# BaseProximity.net
KiCad netlist of a schematic drawn in EAGLE
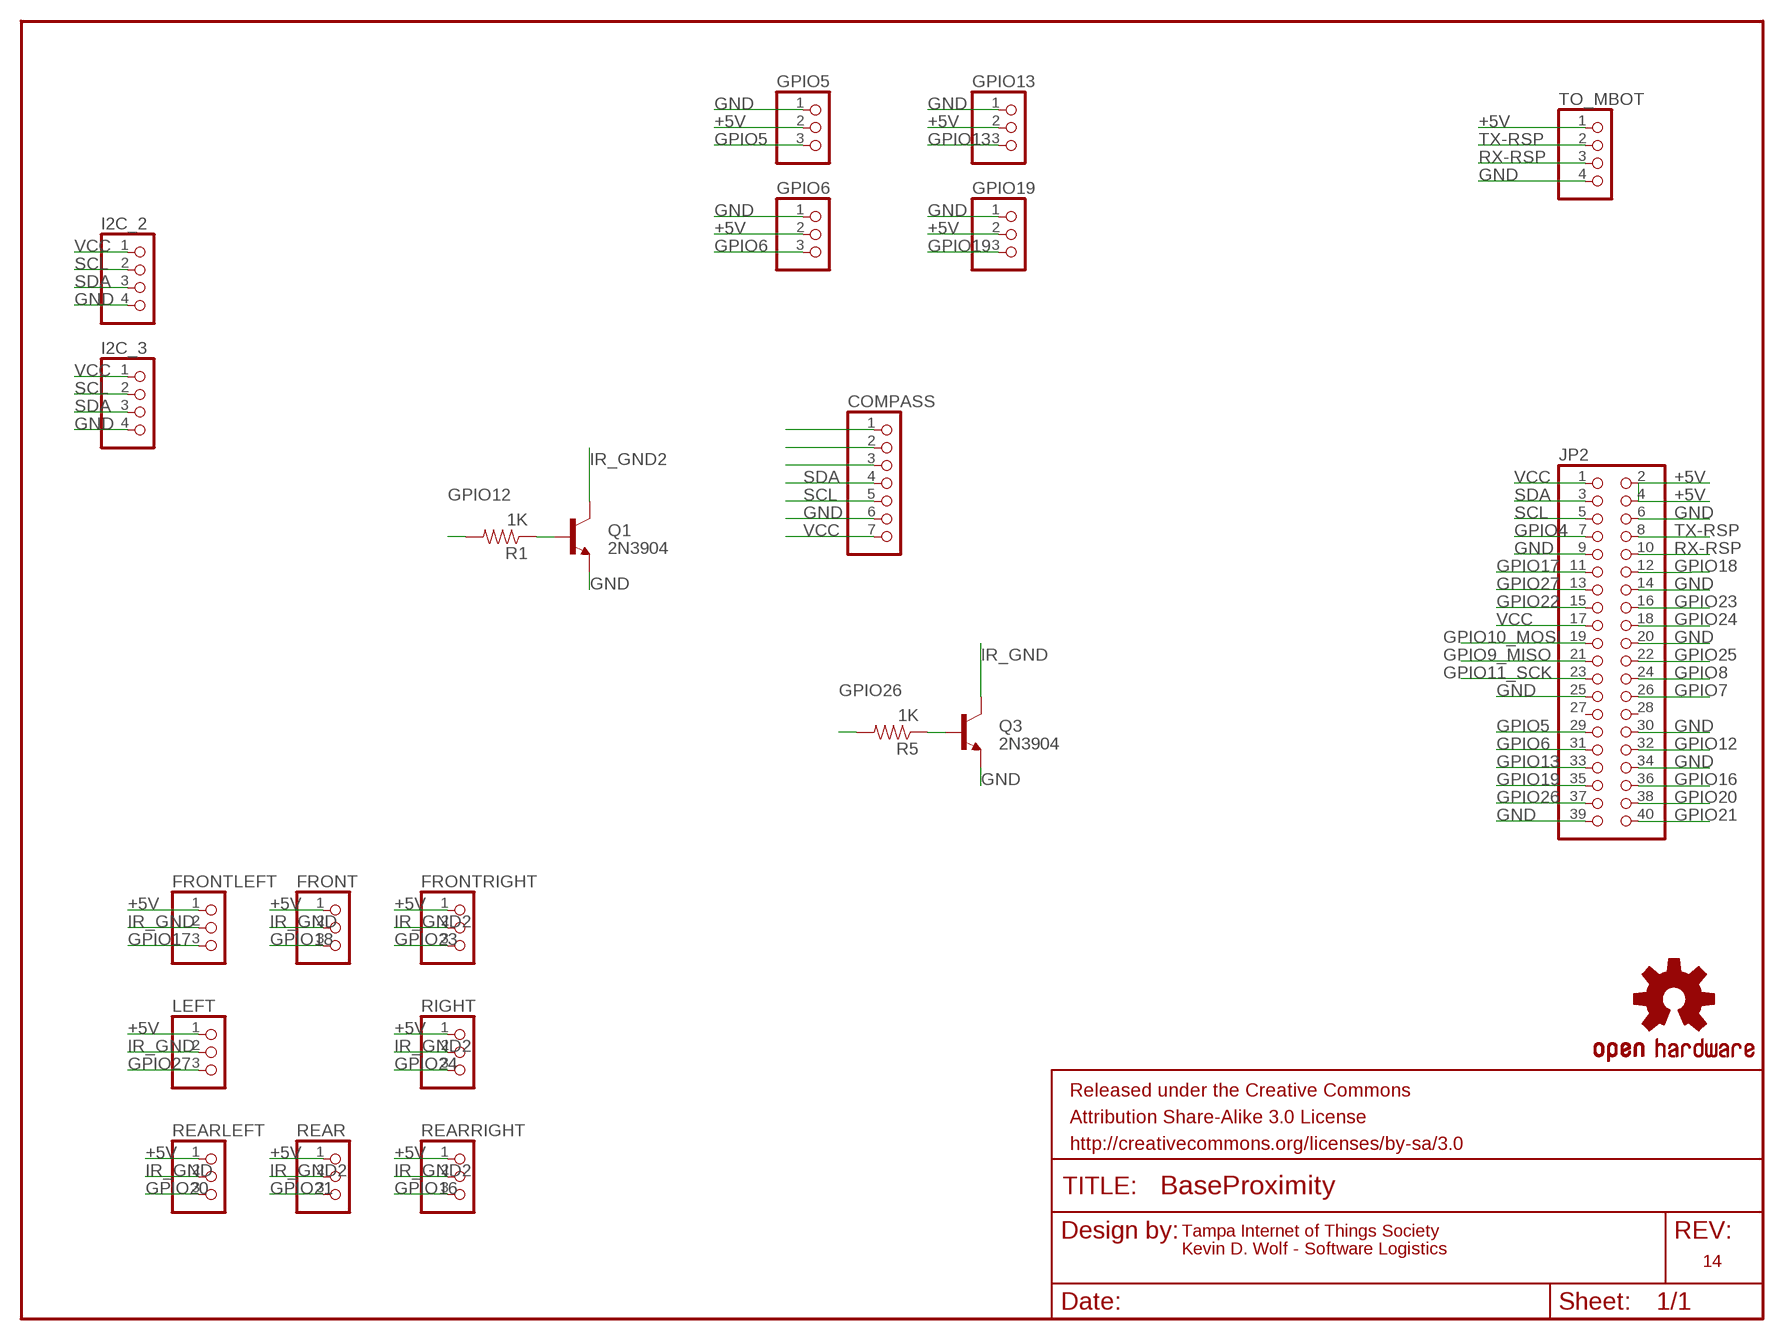
[diagram p0: schematic, sheet 1]

(export (version "E")
  (design (tool "Eeschema 10.0.6"))
  (components
    (comp (ref "COMPASS")
      (value "PINHD-1X7")
      (footprint "eagle-import:1X07")
      (libsource (lib "eagle-import") (part "PINHD-1X7"))
    )
    (comp (ref "FRAME1")
      (value "FRAME-LETTER")
      (footprint "eagle-import:CREATIVE_COMMONS")
      (libsource (lib "eagle-import") (part "FRAME-LETTER"))
    )
    (comp (ref "FRONT")
      (value "PINHD-1X3")
      (footprint "eagle-import:1X03")
      (libsource (lib "eagle-import") (part "PINHD-1X3"))
    )
    (comp (ref "FRONTLEFT")
      (value "PINHD-1X3")
      (footprint "eagle-import:1X03")
      (libsource (lib "eagle-import") (part "PINHD-1X3"))
    )
    (comp (ref "FRONTRIGHT")
      (value "PINHD-1X3")
      (footprint "eagle-import:1X03")
      (libsource (lib "eagle-import") (part "PINHD-1X3"))
    )
    (comp (ref "GPIO5")
      (value "PINHD-1X3")
      (footprint "eagle-import:1X03")
      (libsource (lib "eagle-import") (part "PINHD-1X3"))
    )
    (comp (ref "GPIO6")
      (value "PINHD-1X3")
      (footprint "eagle-import:1X03")
      (libsource (lib "eagle-import") (part "PINHD-1X3"))
    )
    (comp (ref "GPIO13")
      (value "PINHD-1X3")
      (footprint "eagle-import:1X03")
      (libsource (lib "eagle-import") (part "PINHD-1X3"))
    )
    (comp (ref "GPIO19")
      (value "PINHD-1X3")
      (footprint "eagle-import:1X03")
      (libsource (lib "eagle-import") (part "PINHD-1X3"))
    )
    (comp (ref "I2C_2")
      (value "PINHD-1X4")
      (footprint "eagle-import:1X04")
      (libsource (lib "eagle-import") (part "PINHD-1X4"))
    )
    (comp (ref "I2C_3")
      (value "PINHD-1X4")
      (footprint "eagle-import:1X04")
      (libsource (lib "eagle-import") (part "PINHD-1X4"))
    )
    (comp (ref "JP2")
      (value "PINHD-2X20")
      (footprint "eagle-import:2X20")
      (libsource (lib "eagle-import") (part "PINHD-2X20"))
    )
    (comp (ref "LEFT")
      (value "PINHD-1X3")
      (footprint "eagle-import:1X03")
      (libsource (lib "eagle-import") (part "PINHD-1X3"))
    )
    (comp (ref "Q1")
      (value "2N3904")
      (footprint "eagle-import:TO-92-EZ")
      (libsource (lib "eagle-import") (part "TRANSISTOR_NPN2N3904-EZ"))
    )
    (comp (ref "Q3")
      (value "2N3904")
      (footprint "eagle-import:TO-92-EZ")
      (libsource (lib "eagle-import") (part "TRANSISTOR_NPN2N3904-EZ"))
    )
    (comp (ref "R1")
      (value "1K")
      (footprint "eagle-import:AXIAL-0.3EZ")
      (libsource (lib "eagle-import") (part "1KOHM-1/4W-1%(PTH)HORIZ-KIT"))
    )
    (comp (ref "R5")
      (value "1K")
      (footprint "eagle-import:AXIAL-0.3EZ")
      (libsource (lib "eagle-import") (part "1KOHM-1/4W-1%(PTH)HORIZ-KIT"))
    )
    (comp (ref "REAR")
      (value "PINHD-1X3")
      (footprint "eagle-import:1X03")
      (libsource (lib "eagle-import") (part "PINHD-1X3"))
    )
    (comp (ref "REARLEFT")
      (value "PINHD-1X3")
      (footprint "eagle-import:1X03")
      (libsource (lib "eagle-import") (part "PINHD-1X3"))
    )
    (comp (ref "REARRIGHT")
      (value "PINHD-1X3")
      (footprint "eagle-import:1X03")
      (libsource (lib "eagle-import") (part "PINHD-1X3"))
    )
    (comp (ref "RIGHT")
      (value "PINHD-1X3")
      (footprint "eagle-import:1X03")
      (libsource (lib "eagle-import") (part "PINHD-1X3"))
    )
    (comp (ref "TO_MBOT")
      (value "PINHD-1X4")
      (footprint "eagle-import:1X04")
      (libsource (lib "eagle-import") (part "PINHD-1X4"))
    )
    (comp (ref "U$3")
      (value "OSHW-LOGOS")
      (footprint "eagle-import:OSHW-LOGO-S")
      (libsource (lib "eagle-import") (part "OSHW-LOGOS"))
    )
  )
  (nets
    (net (code "1") (name "/+5V") (class "Default")
      (node (ref "FRONT") (pin "1") (pinfunction "1_1") (pintype "passive"))
      (node (ref "FRONTLEFT") (pin "1") (pinfunction "1_1") (pintype "passive"))
      (node (ref "FRONTRIGHT") (pin "1") (pinfunction "1_1") (pintype "passive"))
      (node (ref "GPIO13") (pin "2") (pinfunction "2_2") (pintype "passive"))
      (node (ref "GPIO19") (pin "2") (pinfunction "2_2") (pintype "passive"))
      (node (ref "GPIO5") (pin "2") (pinfunction "2_2") (pintype "passive"))
      (node (ref "GPIO6") (pin "2") (pinfunction "2_2") (pintype "passive"))
      (node (ref "JP2") (pin "2") (pinfunction "2_2") (pintype "passive"))
      (node (ref "JP2") (pin "4") (pinfunction "4_4") (pintype "passive"))
      (node (ref "LEFT") (pin "1") (pinfunction "1_1") (pintype "passive"))
      (node (ref "REAR") (pin "1") (pinfunction "1_1") (pintype "passive"))
      (node (ref "REARLEFT") (pin "1") (pinfunction "1_1") (pintype "passive"))
      (node (ref "REARRIGHT") (pin "1") (pinfunction "1_1") (pintype "passive"))
      (node (ref "RIGHT") (pin "1") (pinfunction "1_1") (pintype "passive"))
      (node (ref "TO_MBOT") (pin "1") (pinfunction "1_1") (pintype "passive"))
    )
    (net (code "2") (name "/GND") (class "Default")
      (node (ref "COMPASS") (pin "6") (pinfunction "6_6") (pintype "passive"))
      (node (ref "GPIO13") (pin "1") (pinfunction "1_1") (pintype "passive"))
      (node (ref "GPIO19") (pin "1") (pinfunction "1_1") (pintype "passive"))
      (node (ref "GPIO5") (pin "1") (pinfunction "1_1") (pintype "passive"))
      (node (ref "GPIO6") (pin "1") (pinfunction "1_1") (pintype "passive"))
      (node (ref "I2C_2") (pin "4") (pinfunction "4_4") (pintype "passive"))
      (node (ref "I2C_3") (pin "4") (pinfunction "4_4") (pintype "passive"))
      (node (ref "JP2") (pin "14") (pinfunction "14_14") (pintype "passive"))
      (node (ref "JP2") (pin "20") (pinfunction "20_20") (pintype "passive"))
      (node (ref "JP2") (pin "25") (pinfunction "25_25") (pintype "passive"))
      (node (ref "JP2") (pin "30") (pinfunction "30_30") (pintype "passive"))
      (node (ref "JP2") (pin "34") (pinfunction "34_34") (pintype "passive"))
      (node (ref "JP2") (pin "39") (pinfunction "39_39") (pintype "passive"))
      (node (ref "JP2") (pin "6") (pinfunction "6_6") (pintype "passive"))
      (node (ref "JP2") (pin "9") (pinfunction "9_9") (pintype "passive"))
      (node (ref "Q1") (pin "1") (pinfunction "E_1") (pintype "passive"))
      (node (ref "Q3") (pin "1") (pinfunction "E_1") (pintype "passive"))
      (node (ref "TO_MBOT") (pin "4") (pinfunction "4_4") (pintype "passive"))
    )
    (net (code "3") (name "/GPIO4") (class "Default")
      (node (ref "JP2") (pin "7") (pinfunction "7_7") (pintype "passive"))
    )
    (net (code "4") (name "/GPIO5") (class "Default")
      (node (ref "GPIO5") (pin "3") (pinfunction "3_3") (pintype "passive"))
      (node (ref "JP2") (pin "29") (pinfunction "29_29") (pintype "passive"))
    )
    (net (code "5") (name "/GPIO6") (class "Default")
      (node (ref "GPIO6") (pin "3") (pinfunction "3_3") (pintype "passive"))
      (node (ref "JP2") (pin "31") (pinfunction "31_31") (pintype "passive"))
    )
    (net (code "6") (name "/GPIO7") (class "Default")
      (node (ref "JP2") (pin "26") (pinfunction "26_26") (pintype "passive"))
    )
    (net (code "7") (name "/GPIO8") (class "Default")
      (node (ref "JP2") (pin "24") (pinfunction "24_24") (pintype "passive"))
    )
    (net (code "8") (name "/GPIO9_MISO") (class "Default")
      (node (ref "JP2") (pin "21") (pinfunction "21_21") (pintype "passive"))
    )
    (net (code "9") (name "/GPIO10_MOSI") (class "Default")
      (node (ref "JP2") (pin "19") (pinfunction "19_19") (pintype "passive"))
    )
    (net (code "10") (name "/GPIO11_SCK") (class "Default")
      (node (ref "JP2") (pin "23") (pinfunction "23_23") (pintype "passive"))
    )
    (net (code "11") (name "/GPIO12") (class "Default")
      (node (ref "JP2") (pin "32") (pinfunction "32_32") (pintype "passive"))
      (node (ref "R1") (pin "P$2") (pinfunction "2_P$2") (pintype "passive"))
    )
    (net (code "12") (name "/GPIO13") (class "Default")
      (node (ref "GPIO13") (pin "3") (pinfunction "3_3") (pintype "passive"))
      (node (ref "JP2") (pin "33") (pinfunction "33_33") (pintype "passive"))
    )
    (net (code "13") (name "/GPIO16") (class "Default")
      (node (ref "JP2") (pin "36") (pinfunction "36_36") (pintype "passive"))
      (node (ref "REARRIGHT") (pin "3") (pinfunction "3_3") (pintype "passive"))
    )
    (net (code "14") (name "/GPIO17") (class "Default")
      (node (ref "FRONTLEFT") (pin "3") (pinfunction "3_3") (pintype "passive"))
      (node (ref "JP2") (pin "11") (pinfunction "11_11") (pintype "passive"))
    )
    (net (code "15") (name "/GPIO18") (class "Default")
      (node (ref "FRONT") (pin "3") (pinfunction "3_3") (pintype "passive"))
      (node (ref "JP2") (pin "12") (pinfunction "12_12") (pintype "passive"))
    )
    (net (code "16") (name "/GPIO19") (class "Default")
      (node (ref "GPIO19") (pin "3") (pinfunction "3_3") (pintype "passive"))
      (node (ref "JP2") (pin "35") (pinfunction "35_35") (pintype "passive"))
    )
    (net (code "17") (name "/GPIO20") (class "Default")
      (node (ref "JP2") (pin "38") (pinfunction "38_38") (pintype "passive"))
      (node (ref "REARLEFT") (pin "3") (pinfunction "3_3") (pintype "passive"))
    )
    (net (code "18") (name "/GPIO21") (class "Default")
      (node (ref "JP2") (pin "40") (pinfunction "40_40") (pintype "passive"))
      (node (ref "REAR") (pin "3") (pinfunction "3_3") (pintype "passive"))
    )
    (net (code "19") (name "/GPIO22") (class "Default")
      (node (ref "JP2") (pin "15") (pinfunction "15_15") (pintype "passive"))
    )
    (net (code "20") (name "/GPIO23") (class "Default")
      (node (ref "FRONTRIGHT") (pin "3") (pinfunction "3_3") (pintype "passive"))
      (node (ref "JP2") (pin "16") (pinfunction "16_16") (pintype "passive"))
    )
    (net (code "21") (name "/GPIO24") (class "Default")
      (node (ref "JP2") (pin "18") (pinfunction "18_18") (pintype "passive"))
      (node (ref "RIGHT") (pin "3") (pinfunction "3_3") (pintype "passive"))
    )
    (net (code "22") (name "/GPIO25") (class "Default")
      (node (ref "JP2") (pin "22") (pinfunction "22_22") (pintype "passive"))
    )
    (net (code "23") (name "/GPIO26") (class "Default")
      (node (ref "JP2") (pin "37") (pinfunction "37_37") (pintype "passive"))
      (node (ref "R5") (pin "P$2") (pinfunction "2_P$2") (pintype "passive"))
    )
    (net (code "24") (name "/GPIO27") (class "Default")
      (node (ref "JP2") (pin "13") (pinfunction "13_13") (pintype "passive"))
      (node (ref "LEFT") (pin "3") (pinfunction "3_3") (pintype "passive"))
    )
    (net (code "25") (name "/IR_GND") (class "Default")
      (node (ref "FRONT") (pin "2") (pinfunction "2_2") (pintype "passive"))
      (node (ref "FRONTLEFT") (pin "2") (pinfunction "2_2") (pintype "passive"))
      (node (ref "LEFT") (pin "2") (pinfunction "2_2") (pintype "passive"))
      (node (ref "Q3") (pin "3") (pinfunction "C_3") (pintype "passive"))
      (node (ref "REARLEFT") (pin "2") (pinfunction "2_2") (pintype "passive"))
    )
    (net (code "26") (name "/IR_GND2") (class "Default")
      (node (ref "FRONTRIGHT") (pin "2") (pinfunction "2_2") (pintype "passive"))
      (node (ref "Q1") (pin "3") (pinfunction "C_3") (pintype "passive"))
      (node (ref "REAR") (pin "2") (pinfunction "2_2") (pintype "passive"))
      (node (ref "REARRIGHT") (pin "2") (pinfunction "2_2") (pintype "passive"))
      (node (ref "RIGHT") (pin "2") (pinfunction "2_2") (pintype "passive"))
    )
    (net (code "27") (name "/RX-RSP") (class "Default")
      (node (ref "JP2") (pin "10") (pinfunction "10_10") (pintype "passive"))
      (node (ref "TO_MBOT") (pin "3") (pinfunction "3_3") (pintype "passive"))
    )
    (net (code "28") (name "/SCL") (class "Default")
      (node (ref "COMPASS") (pin "5") (pinfunction "5_5") (pintype "passive"))
      (node (ref "I2C_2") (pin "2") (pinfunction "2_2") (pintype "passive"))
      (node (ref "I2C_3") (pin "2") (pinfunction "2_2") (pintype "passive"))
      (node (ref "JP2") (pin "5") (pinfunction "5_5") (pintype "passive"))
    )
    (net (code "29") (name "/SDA") (class "Default")
      (node (ref "COMPASS") (pin "4") (pinfunction "4_4") (pintype "passive"))
      (node (ref "I2C_2") (pin "3") (pinfunction "3_3") (pintype "passive"))
      (node (ref "I2C_3") (pin "3") (pinfunction "3_3") (pintype "passive"))
      (node (ref "JP2") (pin "3") (pinfunction "3_3") (pintype "passive"))
    )
    (net (code "30") (name "/TX-RSP") (class "Default")
      (node (ref "JP2") (pin "8") (pinfunction "8_8") (pintype "passive"))
      (node (ref "TO_MBOT") (pin "2") (pinfunction "2_2") (pintype "passive"))
    )
    (net (code "31") (name "/VCC") (class "Default")
      (node (ref "COMPASS") (pin "7") (pinfunction "7_7") (pintype "passive"))
      (node (ref "I2C_2") (pin "1") (pinfunction "1_1") (pintype "passive"))
      (node (ref "I2C_3") (pin "1") (pinfunction "1_1") (pintype "passive"))
      (node (ref "JP2") (pin "1") (pinfunction "1_1") (pintype "passive"))
      (node (ref "JP2") (pin "17") (pinfunction "17_17") (pintype "passive"))
    )
    (net (code "32") (name "Net-(Q1-B)") (class "Default")
      (node (ref "Q1") (pin "2") (pinfunction "B_2") (pintype "passive"))
      (node (ref "R1") (pin "P$1") (pinfunction "1_P$1") (pintype "passive"))
    )
    (net (code "33") (name "Net-(Q3-B)") (class "Default")
      (node (ref "Q3") (pin "2") (pinfunction "B_2") (pintype "passive"))
      (node (ref "R5") (pin "P$1") (pinfunction "1_P$1") (pintype "passive"))
    )
    (net (code "34") (name "unconnected-(COMPASS-Pad1)") (class "Default")
      (node (ref "COMPASS") (pin "1") (pinfunction "1_1") (pintype "passive"))
    )
    (net (code "35") (name "unconnected-(COMPASS-Pad2)") (class "Default")
      (node (ref "COMPASS") (pin "2") (pinfunction "2_2") (pintype "passive"))
    )
    (net (code "36") (name "unconnected-(COMPASS-Pad3)") (class "Default")
      (node (ref "COMPASS") (pin "3") (pinfunction "3_3") (pintype "passive"))
    )
    (net (code "37") (name "unconnected-(JP2-Pad27)") (class "Default")
      (node (ref "JP2") (pin "27") (pinfunction "27_27") (pintype "passive"))
    )
    (net (code "38") (name "unconnected-(JP2-Pad28)") (class "Default")
      (node (ref "JP2") (pin "28") (pinfunction "28_28") (pintype "passive"))
    )
  )
)
